# 15_-_PWR_3V3_1V375.net
KiCad netlist of a schematic drawn in Altium Designer
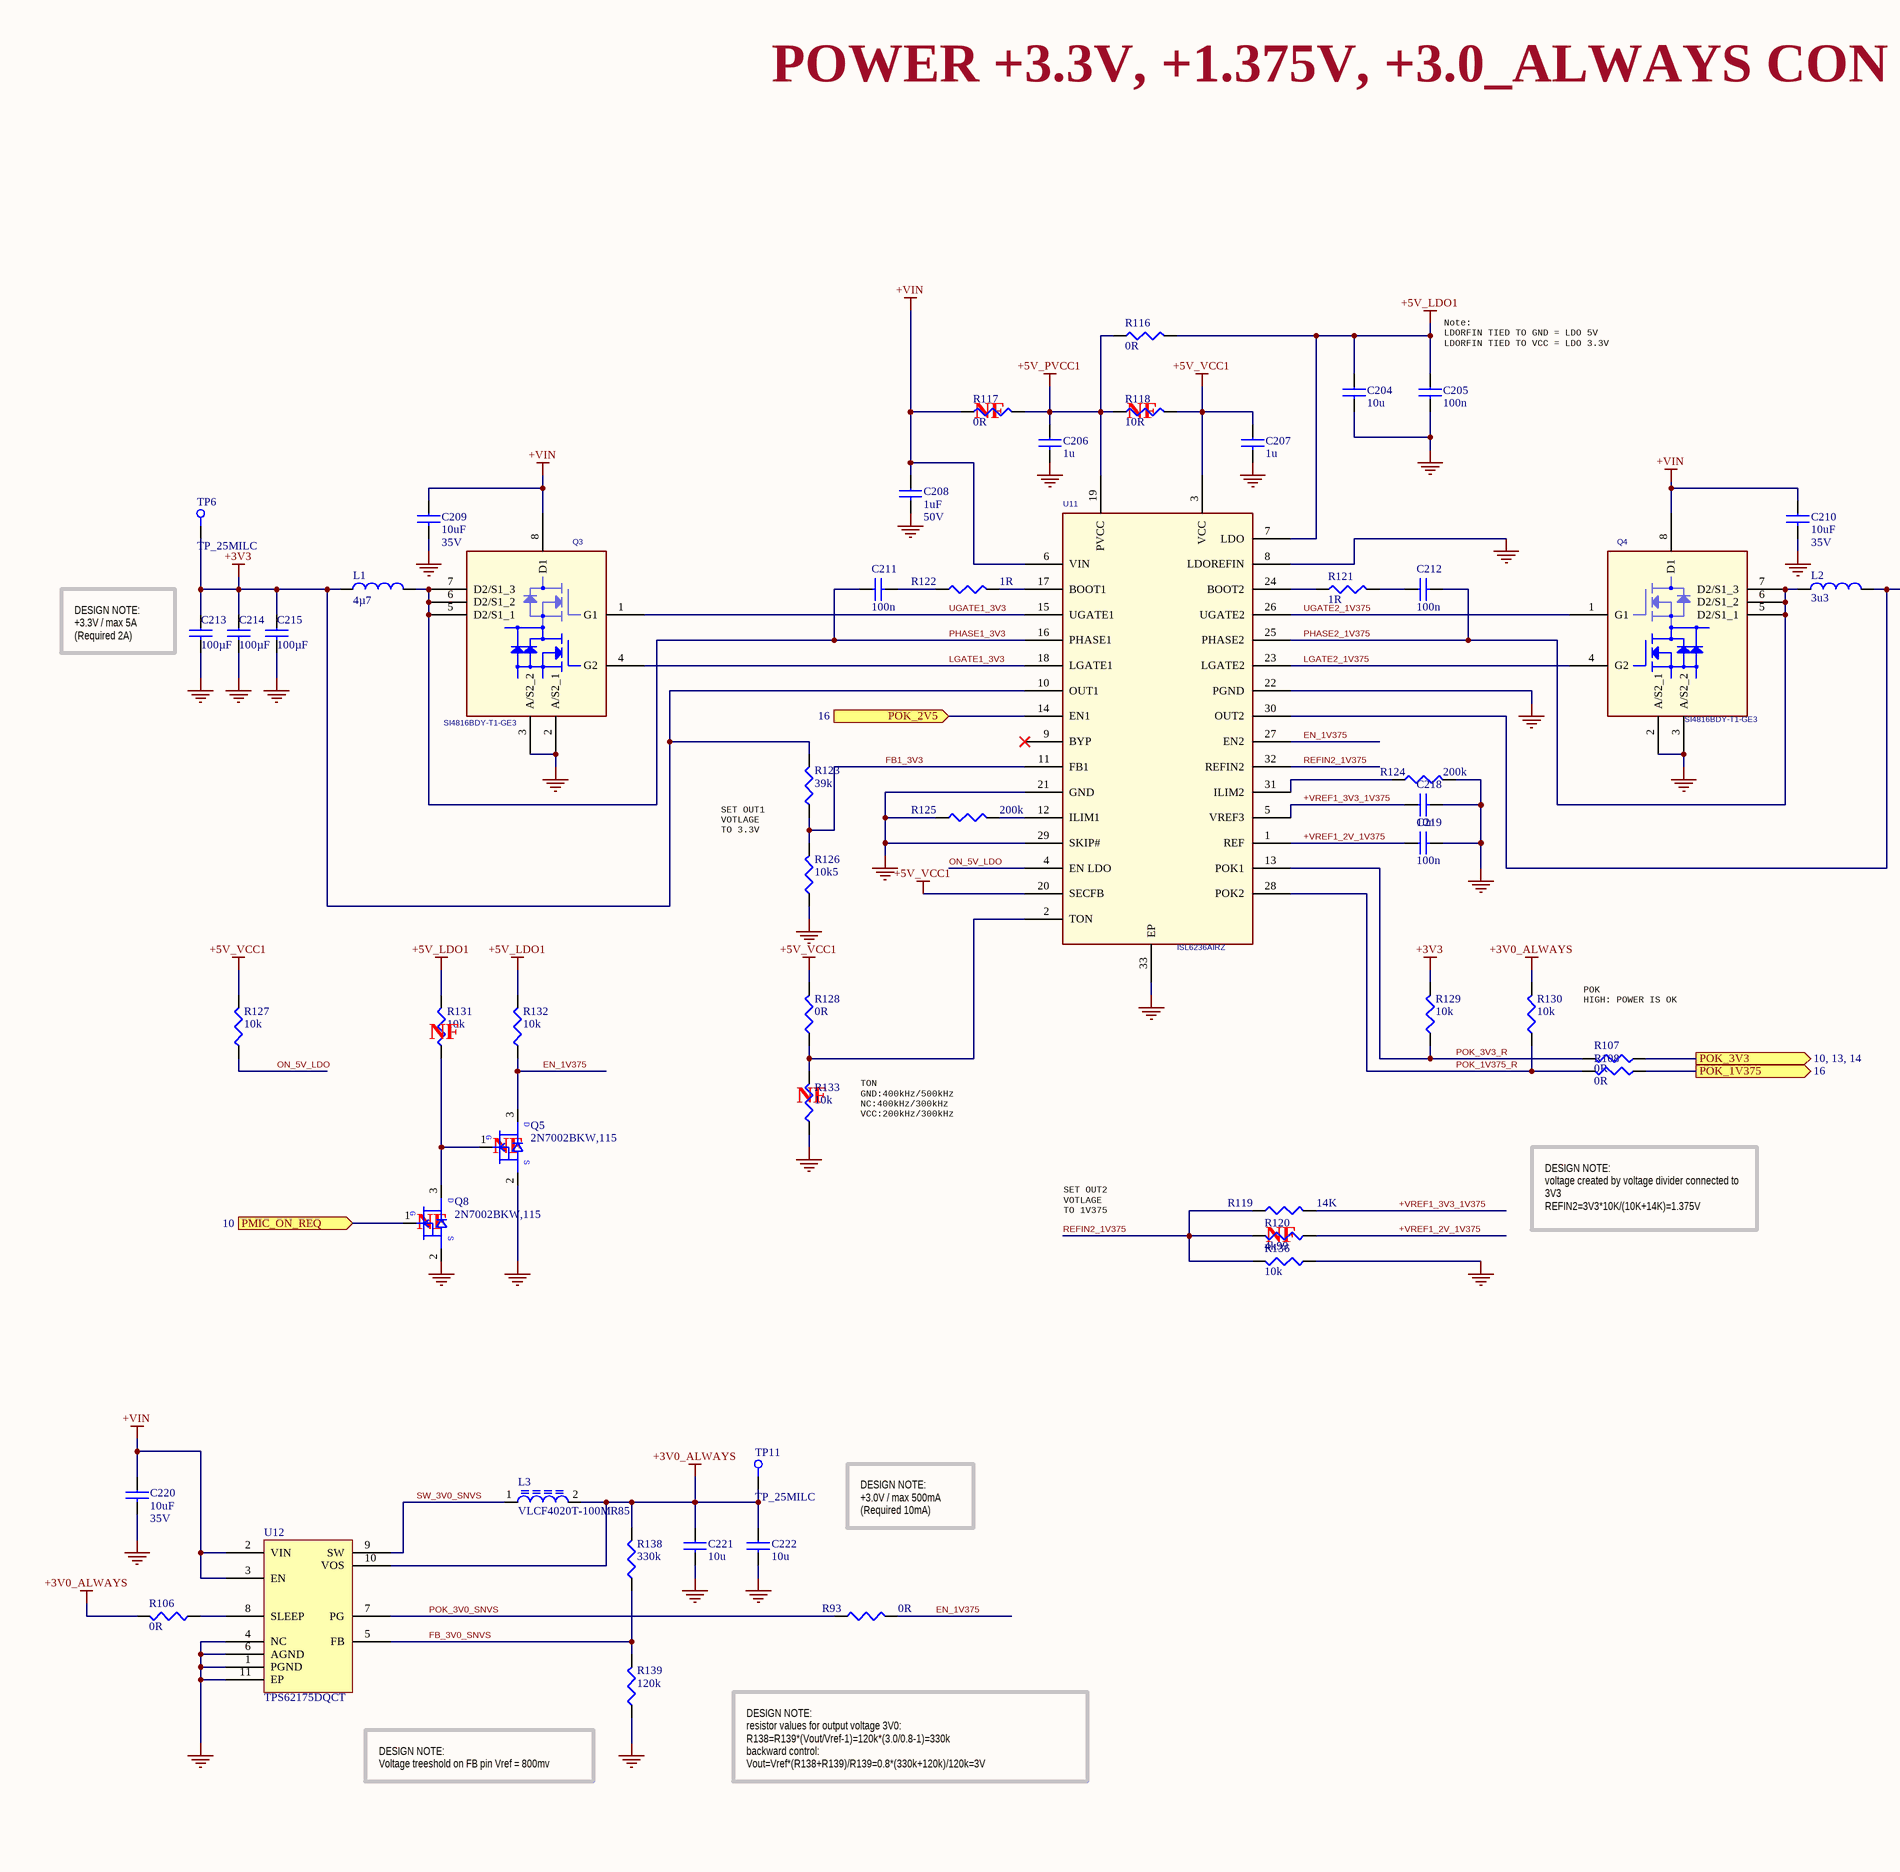
[diagram p0: [15] - PWR 3V3, 1V375.SchDoc, left]
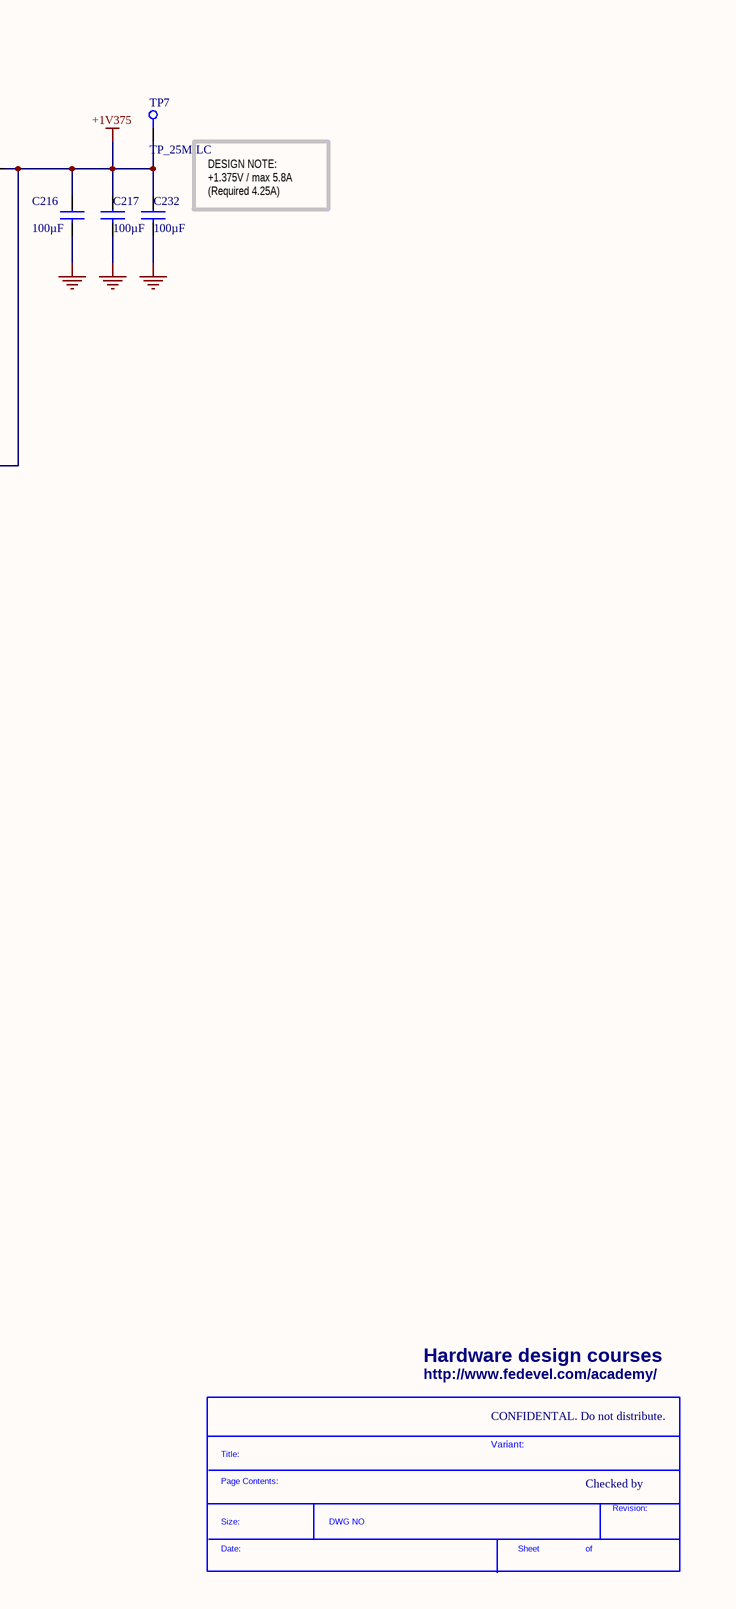
[diagram p1: [15] - PWR 3V3, 1V375.SchDoc, right]

(export (version "E")
  (design (tool "Eeschema 10.0.6"))
  (components
    (comp (ref "C204")
      (value "10u")
      (footprint "C0603")
      (description "CAP CER 10UF 6.3V X5R 20% 0603")
      (fields
        (field (name "MANUFACTURER") "TDK Corporation")
        (field (name "MANUFACTURER PART NUMBER") "C1608X5R0J106M")
      )
      (libsource (lib "iMX6 Rex_V1I1") (part "C1608X5R0J106M"))
    )
    (comp (ref "C205")
      (value "100n")
      (footprint "C0402")
      (description "CAP CER .10UF 50V X5R 10% 0402")
      (fields
        (field (name "MANUFACTURER") "TDK Corporation")
        (field (name "MANUFACTURER PART NUMBER") "C1005X5R1H104K")
      )
      (libsource (lib "iMX6 Rex_V1I1") (part "C1005X5R1H104K"))
    )
    (comp (ref "C206")
      (value "1u")
      (footprint "C0402")
      (description "CAP CER 1.0UF 16V X5R 0402")
      (fields
        (field (name "MANUFACTURER") "TDK Corporation")
        (field (name "MANUFACTURER PART NUMBER") "C1005X5R1C105K")
      )
      (libsource (lib "iMX6 Rex_V1I1") (part "C1005X5R1C105K"))
    )
    (comp (ref "C207")
      (value "1u")
      (footprint "C0402")
      (description "CAP CER 1.0UF 16V X5R 0402")
      (fields
        (field (name "MANUFACTURER") "TDK Corporation")
        (field (name "MANUFACTURER PART NUMBER") "C1005X5R1C105K")
      )
      (libsource (lib "iMX6 Rex_V1I1") (part "C1005X5R1C105K"))
    )
    (comp (ref "C208")
      (value "1uF")
      (footprint "C0805")
      (description "CAP CER 1UF 50V X7R 0805")
      (fields
        (field (name "MANUFACTURER") "Murata Electronics North America")
        (field (name "MANUFACTURER PART NUMBER") "GRM21BR71H105KA12L")
        (field (name "VOLTAGE - RATED") "50V")
      )
      (libsource (lib "iMX6 Rex_V1I1") (part "GRM21BR71H105KA12L"))
    )
    (comp (ref "C209")
      (value "10uF")
      (footprint "C1206")
      (description "CAP CER 10UF 35V X5R 1206")
      (fields
        (field (name "MANUFACTURER") "Murata Electronics North America")
        (field (name "MANUFACTURER PART NUMBER") "GRM31CR6YA106KA12L")
        (field (name "VOLTAGE - RATED") "35V")
      )
      (libsource (lib "iMX6 Rex_V1I1") (part "GRM31CR6YA106KA12L"))
    )
    (comp (ref "C210")
      (value "10uF")
      (footprint "C1206")
      (description "CAP CER 10UF 35V X5R 1206")
      (fields
        (field (name "MANUFACTURER") "Murata Electronics North America")
        (field (name "MANUFACTURER PART NUMBER") "GRM31CR6YA106KA12L")
        (field (name "VOLTAGE - RATED") "35V")
      )
      (libsource (lib "iMX6 Rex_V1I1") (part "GRM31CR6YA106KA12L"))
    )
    (comp (ref "C211")
      (value "100n")
      (footprint "C0402")
      (description "CAP CER .10UF 50V X5R 10% 0402")
      (fields
        (field (name "MANUFACTURER") "TDK Corporation")
        (field (name "MANUFACTURER PART NUMBER") "C1005X5R1H104K")
      )
      (libsource (lib "iMX6 Rex_V1I1") (part "C1005X5R1H104K"))
    )
    (comp (ref "C212")
      (value "100n")
      (footprint "C0402")
      (description "CAP CER .10UF 50V X5R 10% 0402")
      (fields
        (field (name "MANUFACTURER") "TDK Corporation")
        (field (name "MANUFACTURER PART NUMBER") "C1005X5R1H104K")
      )
      (libsource (lib "iMX6 Rex_V1I1") (part "C1005X5R1H104K"))
    )
    (comp (ref "C213")
      (value "100µF")
      (footprint "C1206")
      (description "CAP CER 100UF 10V X5R 20% 1206")
      (fields
        (field (name "MANUFACTURER") "TDK Corporation")
        (field (name "MANUFACTURER PART NUMBER") "C3216X5R1A107M")
      )
      (libsource (lib "iMX6 Rex_V1I1") (part "C3216X5R1A107M"))
    )
    (comp (ref "C214")
      (value "100µF")
      (footprint "C1206")
      (description "CAP CER 100UF 10V X5R 20% 1206")
      (fields
        (field (name "MANUFACTURER") "TDK Corporation")
        (field (name "MANUFACTURER PART NUMBER") "C3216X5R1A107M")
      )
      (libsource (lib "iMX6 Rex_V1I1") (part "C3216X5R1A107M"))
    )
    (comp (ref "C215")
      (value "100µF")
      (footprint "C1206")
      (description "CAP CER 100UF 10V X5R 20% 1206")
      (fields
        (field (name "MANUFACTURER") "TDK Corporation")
        (field (name "MANUFACTURER PART NUMBER") "C3216X5R1A107M")
      )
      (libsource (lib "iMX6 Rex_V1I1") (part "C3216X5R1A107M"))
    )
    (comp (ref "C216")
      (value "100µF")
      (footprint "C1206")
      (description "CAP CER 100UF 10V X5R 20% 1206")
      (fields
        (field (name "MANUFACTURER") "TDK Corporation")
        (field (name "MANUFACTURER PART NUMBER") "C3216X5R1A107M")
      )
      (libsource (lib "iMX6 Rex_V1I1") (part "C3216X5R1A107M"))
    )
    (comp (ref "C217")
      (value "100µF")
      (footprint "C1206")
      (description "CAP CER 100UF 10V X5R 20% 1206")
      (fields
        (field (name "MANUFACTURER") "TDK Corporation")
        (field (name "MANUFACTURER PART NUMBER") "C3216X5R1A107M")
      )
      (libsource (lib "iMX6 Rex_V1I1") (part "C3216X5R1A107M"))
    )
    (comp (ref "C218")
      (value "10n")
      (footprint "C0402")
      (description "CAP CER 10000PF 16V X7R 10% 0402")
      (fields
        (field (name "MANUFACTURER") "TDK Corporation")
        (field (name "MANUFACTURER PART NUMBER") "C1005X7R1C103K")
      )
      (libsource (lib "iMX6 Rex_V1I1") (part "C1005X7R1C103K"))
    )
    (comp (ref "C219")
      (value "100n")
      (footprint "C0402")
      (description "CAP CER .10UF 50V X5R 10% 0402")
      (fields
        (field (name "MANUFACTURER") "TDK Corporation")
        (field (name "MANUFACTURER PART NUMBER") "C1005X5R1H104K")
      )
      (libsource (lib "iMX6 Rex_V1I1") (part "C1005X5R1H104K"))
    )
    (comp (ref "C220")
      (value "10uF")
      (footprint "C1206")
      (description "CAP CER 10UF 35V X5R 1206")
      (fields
        (field (name "MANUFACTURER") "Murata Electronics North America")
        (field (name "MANUFACTURER PART NUMBER") "GRM31CR6YA106KA12L")
        (field (name "VOLTAGE - RATED") "35V")
      )
      (libsource (lib "iMX6 Rex_V1I1") (part "GRM31CR6YA106KA12L"))
    )
    (comp (ref "C221")
      (value "10u")
      (footprint "C0603")
      (description "CAP CER 10UF 6.3V X5R 20% 0603")
      (fields
        (field (name "MANUFACTURER") "TDK Corporation")
        (field (name "MANUFACTURER PART NUMBER") "C1608X5R0J106M")
      )
      (libsource (lib "iMX6 Rex_V1I1") (part "C1608X5R0J106M"))
    )
    (comp (ref "C222")
      (value "10u")
      (footprint "C0603")
      (description "CAP CER 10UF 6.3V X5R 20% 0603")
      (fields
        (field (name "MANUFACTURER") "TDK Corporation")
        (field (name "MANUFACTURER PART NUMBER") "C1608X5R0J106M")
      )
      (libsource (lib "iMX6 Rex_V1I1") (part "C1608X5R0J106M"))
    )
    (comp (ref "C232")
      (value "100µF")
      (footprint "C1206")
      (description "CAP CER 100UF 10V X5R 20% 1206")
      (fields
        (field (name "MANUFACTURER") "TDK Corporation")
        (field (name "MANUFACTURER PART NUMBER") "C3216X5R1A107M")
      )
      (libsource (lib "iMX6 Rex_V1I1") (part "C3216X5R1A107M"))
    )
    (comp (ref "L1")
      (value "4µ7")
      (footprint "IHLP_255MILx270MIL")
      (description "INDUCTOR POWER 4.7UH 5.5A SMD")
      (fields
        (field (name "MANUFACTURER") "Vishay/Dale")
        (field (name "MANUFACTURER PART NUMBER") "IHLP2525CZER4R7M01")
      )
      (libsource (lib "iMX6 Rex_V1I1") (part "IHLP2525CZER4R7M01"))
    )
    (comp (ref "L2")
      (value "3u3")
      (footprint "IHLP_255MILx270MIL")
      (description "INDUCTOR POWER 3.3UH 6A SMD")
      (fields
        (field (name "MANUFACTURER") "Vishay Dale")
        (field (name "MANUFACTURER PART NUMBER") "IHLP2525CZER3R3M01")
        (field (name ".CHECKED PCB") "RF")
        (field (name ".CHECKED SCH") "RF")
      )
      (libsource (lib "iMX6 Rex_V1I1") (part "IHLP2525CZER3R3M01"))
    )
    (comp (ref "L3")
      (value "VLCF4020T-100MR85")
      (footprint "VLCF4020")
      (description "INDUCTOR POWER 10UH .85A SMD")
      (fields
        (field (name "MANUFACTURER") "TDK Corporation")
        (field (name "TOLERANCE") "±20%")
        (field (name ".CREATOR") "MM")
        (field (name ".CHECKED PCB") "MM, checked by RF")
        (field (name ".CHECKED SCH") "MM, checked by RF")
      )
      (libsource (lib "iMX6 Rex_V1I1") (part "VLCF4020T-100MR85"))
    )
    (comp (ref "Q3")
      (value "SI4816BDY-T1-GE3")
      (footprint "8_SOIC_3.9MM")
      (description "MOSFET DL N-CH 30V 6.8A 8-SOIC")
      (fields (field (name "MANUFACTURER") "Vishay/Siliconix"))
      (libsource (lib "iMX6 Rex_V1I1") (part "SI4816BDY-T1-GE3"))
    )
    (comp (ref "Q4")
      (value "SI4816BDY-T1-GE3")
      (footprint "8_SOIC_3.9MM")
      (description "MOSFET DL N-CH 30V 6.8A 8-SOIC")
      (fields (field (name "MANUFACTURER") "Vishay/Siliconix"))
      (libsource (lib "iMX6 Rex_V1I1") (part "SI4816BDY-T1-GE3"))
    )
    (comp (ref "Q5")
      (value "2N7002BKW,115")
      (footprint "SC70_SOT323")
      (description "MOSFET N-CH 60V 310MA SOT323")
      (fields
        (field (name "MANUFACTURER") "NXP Semiconductors")
        (field (name ".CHECKED PCB") "RF")
        (field (name ".CHECKED SCH") "RF")
      )
      (libsource (lib "iMX6 Rex_V1I1") (part "2N7002BKW,115"))
    )
    (comp (ref "Q8")
      (value "2N7002BKW,115")
      (footprint "SC70_SOT323")
      (description "MOSFET N-CH 60V 310MA SOT323")
      (fields
        (field (name "MANUFACTURER") "NXP Semiconductors")
        (field (name ".CHECKED PCB") "RF")
        (field (name ".CHECKED SCH") "RF")
      )
      (libsource (lib "iMX6 Rex_V1I1") (part "2N7002BKW,115"))
    )
    (comp (ref "R93")
      (value "0R")
      (footprint "R0402")
      (description "RES 0.0 OHM 1/16W 0402 SMD")
      (fields
        (field (name "MANUFACTURER") "Yageo")
        (field (name "MANUFACTURER PART NUMBER") "RC0402JR-070RL")
      )
      (libsource (lib "iMX6 Rex_V1I1") (part "RC0402JR-070RL"))
    )
    (comp (ref "R106")
      (value "0R")
      (footprint "R0402")
      (description "RES 0.0 OHM 1/16W 0402 SMD")
      (fields
        (field (name "MANUFACTURER") "Yageo")
        (field (name "MANUFACTURER PART NUMBER") "RC0402JR-070RL")
      )
      (libsource (lib "iMX6 Rex_V1I1") (part "RC0402JR-070RL"))
    )
    (comp (ref "R107")
      (value "0R")
      (footprint "R0402")
      (description "RES 0.0 OHM 1/16W 0402 SMD")
      (fields
        (field (name "MANUFACTURER") "Yageo")
        (field (name "MANUFACTURER PART NUMBER") "RC0402JR-070RL")
      )
      (libsource (lib "iMX6 Rex_V1I1") (part "RC0402JR-070RL"))
    )
    (comp (ref "R108")
      (value "0R")
      (footprint "R0402")
      (description "RES 0.0 OHM 1/16W 0402 SMD")
      (fields
        (field (name "MANUFACTURER") "Yageo")
        (field (name "MANUFACTURER PART NUMBER") "RC0402JR-070RL")
      )
      (libsource (lib "iMX6 Rex_V1I1") (part "RC0402JR-070RL"))
    )
    (comp (ref "R116")
      (value "0R")
      (footprint "R0402")
      (description "RES 0.0 OHM 1/16W 0402 SMD")
      (fields
        (field (name "MANUFACTURER") "Yageo")
        (field (name "MANUFACTURER PART NUMBER") "RC0402JR-070RL")
      )
      (libsource (lib "iMX6 Rex_V1I1") (part "RC0402JR-070RL"))
    )
    (comp (ref "R117")
      (value "0R")
      (footprint "R0402")
      (description "RES 0.0 OHM 1/16W 0402 SMD")
      (fields
        (field (name "MANUFACTURER") "Yageo")
        (field (name "MANUFACTURER PART NUMBER") "RC0402JR-070RL")
      )
      (libsource (lib "iMX6 Rex_V1I1") (part "RC0402JR-070RL"))
    )
    (comp (ref "R118")
      (value "10R")
      (footprint "R0402")
      (description "RES 10.0 OHM 1/16W 1% 0402 SMD")
      (fields
        (field (name "MANUFACTURER") "Yageo")
        (field (name "MANUFACTURER PART NUMBER") "RC0402FR-0710RL")
      )
      (libsource (lib "iMX6 Rex_V1I1") (part "RC0402FR-0710RL"))
    )
    (comp (ref "R119")
      (value "14K")
      (footprint "R0402")
      (description "RES 14.0K OHM 1/16W 1% 0402 SMD")
      (fields
        (field (name "MANUFACTURER") "Yageo")
        (field (name "MANUFACTURER PART NUMBER") "RC0402FR-0714KL")
        (field (name "CREATOR") "MM")
        (field (name ".CHECKED PCB") "RF, used by MM")
        (field (name ".CHECKED SCH") "MM, checked by RF")
        (field (name ".CREATOR") "MM")
      )
      (libsource (lib "iMX6 Rex_V1I1") (part "RC0402FR-0714KL"))
    )
    (comp (ref "R120")
      (value "4k99")
      (footprint "R0402")
      (description "RES TF 4.99K OHM 1% 1/16W 0402")
      (fields
        (field (name "MANUFACTURER") "Stackpole Electronics Inc")
        (field (name "MANUFACTURER PART NUMBER") "RMCF0402FT4K99")
      )
      (libsource (lib "iMX6 Rex_V1I1") (part "RMCF0402FT4K99"))
    )
    (comp (ref "R121")
      (value "1R")
      (footprint "R0402")
      (description "RES 1.00 OHM 1/16W 1% 0402 SM")
      (fields
        (field (name "MANUFACTURER") "Yageo")
        (field (name "MANUFACTURER PART NUMBER") "RC0402FR-071RL")
      )
      (libsource (lib "iMX6 Rex_V1I1") (part "RC0402FR-071RL"))
    )
    (comp (ref "R122")
      (value "1R")
      (footprint "R0402")
      (description "RES 1.00 OHM 1/16W 1% 0402 SM")
      (fields
        (field (name "MANUFACTURER") "Yageo")
        (field (name "MANUFACTURER PART NUMBER") "RC0402FR-071RL")
      )
      (libsource (lib "iMX6 Rex_V1I1") (part "RC0402FR-071RL"))
    )
    (comp (ref "R123")
      (value "39k")
      (footprint "R0402")
      (description "RES 39.0K OHM 1/16W 1% 0402 SMD")
      (fields
        (field (name "MANUFACTURER") "Yageo")
        (field (name "MANUFACTURER PART NUMBER") "RC0402FR-0739KL")
      )
      (libsource (lib "iMX6 Rex_V1I1") (part "RC0402FR-0739KL"))
    )
    (comp (ref "R124")
      (value "200k")
      (footprint "R0402")
      (description "RES 200K OHM 1/16W 1% 0402 SMD")
      (fields
        (field (name "MANUFACTURER") "Yageo")
        (field (name "MANUFACTURER PART NUMBER") "RC0402FR-07200KL")
      )
      (libsource (lib "iMX6 Rex_V1I1") (part "RC0402FR-07200KL"))
    )
    (comp (ref "R125")
      (value "200k")
      (footprint "R0402")
      (description "RES 200K OHM 1/16W 1% 0402 SMD")
      (fields
        (field (name "MANUFACTURER") "Yageo")
        (field (name "MANUFACTURER PART NUMBER") "RC0402FR-07200KL")
      )
      (libsource (lib "iMX6 Rex_V1I1") (part "RC0402FR-07200KL"))
    )
    (comp (ref "R126")
      (value "10k5")
      (footprint "R0402")
      (description "RES 10.5K OHM 1/16W 1% 0402 SMD")
      (fields
        (field (name "MANUFACTURER") "Vishay/Dale")
        (field (name "MANUFACTURER PART NUMBER") "CRCW040210K5FKED")
      )
      (libsource (lib "iMX6 Rex_V1I1") (part "CRCW040210K5FKED"))
    )
    (comp (ref "R127")
      (value "10k")
      (footprint "R0402")
      (description "RES 10.0K OHM 1/16W 1% 0402 SMD")
      (fields
        (field (name "MANUFACTURER") "Yageo")
        (field (name "MANUFACTURER PART NUMBER") "RC0402FR-0710KL")
      )
      (libsource (lib "iMX6 Rex_V1I1") (part "RC0402FR-0710KL"))
    )
    (comp (ref "R128")
      (value "0R")
      (footprint "R0402")
      (description "RES 0.0 OHM 1/16W 0402 SMD")
      (fields
        (field (name "MANUFACTURER") "Yageo")
        (field (name "MANUFACTURER PART NUMBER") "RC0402JR-070RL")
      )
      (libsource (lib "iMX6 Rex_V1I1") (part "RC0402JR-070RL"))
    )
    (comp (ref "R129")
      (value "10k")
      (footprint "R0402")
      (description "RES 10.0K OHM 1/16W 1% 0402 SMD")
      (fields
        (field (name "MANUFACTURER") "Yageo")
        (field (name "MANUFACTURER PART NUMBER") "RC0402FR-0710KL")
      )
      (libsource (lib "iMX6 Rex_V1I1") (part "RC0402FR-0710KL"))
    )
    (comp (ref "R130")
      (value "10k")
      (footprint "R0402")
      (description "RES 10.0K OHM 1/16W 1% 0402 SMD")
      (fields
        (field (name "MANUFACTURER") "Yageo")
        (field (name "MANUFACTURER PART NUMBER") "RC0402FR-0710KL")
      )
      (libsource (lib "iMX6 Rex_V1I1") (part "RC0402FR-0710KL"))
    )
    (comp (ref "R131")
      (value "10k")
      (footprint "R0402")
      (description "RES 10.0K OHM 1/16W 1% 0402 SMD")
      (fields
        (field (name "MANUFACTURER") "Yageo")
        (field (name "MANUFACTURER PART NUMBER") "RC0402FR-0710KL")
      )
      (libsource (lib "iMX6 Rex_V1I1") (part "RC0402FR-0710KL"))
    )
    (comp (ref "R132")
      (value "10k")
      (footprint "R0402")
      (description "RES 10.0K OHM 1/16W 1% 0402 SMD")
      (fields
        (field (name "MANUFACTURER") "Yageo")
        (field (name "MANUFACTURER PART NUMBER") "RC0402FR-0710KL")
      )
      (libsource (lib "iMX6 Rex_V1I1") (part "RC0402FR-0710KL"))
    )
    (comp (ref "R133")
      (value "10k")
      (footprint "R0402")
      (description "RES 10.0K OHM 1/16W 1% 0402 SMD")
      (fields
        (field (name "MANUFACTURER") "Yageo")
        (field (name "MANUFACTURER PART NUMBER") "RC0402FR-0710KL")
      )
      (libsource (lib "iMX6 Rex_V1I1") (part "RC0402FR-0710KL"))
    )
    (comp (ref "R136")
      (value "10k")
      (footprint "R0402")
      (description "RES 10.0K OHM 1/16W 1% 0402 SMD")
      (fields
        (field (name "MANUFACTURER") "Yageo")
        (field (name "MANUFACTURER PART NUMBER") "RC0402FR-0710KL")
      )
      (libsource (lib "iMX6 Rex_V1I1") (part "RC0402FR-0710KL"))
    )
    (comp (ref "R138")
      (value "330k")
      (footprint "R0402")
      (description "RES 330K OHM 1/16W 1% 0402 SMD")
      (fields
        (field (name "MANUFACTURER") "Vishay Dale")
        (field (name "MANUFACTURER PART NUMBER") "CRCW0402330KFKED")
        (field (name ".CHECKED PCB") "RF")
        (field (name ".CHECKED SCH") "RF")
      )
      (libsource (lib "iMX6 Rex_V1I1") (part "CRCW0402330KFKED"))
    )
    (comp (ref "R139")
      (value "120k")
      (footprint "R0402")
      (description "RES 120K OHM 1/16W 1% 0402 SMD")
      (fields
        (field (name "MANUFACTURER") "Yageo")
        (field (name "MANUFACTURER PART NUMBER") "RC0402FR-07120KL")
        (field (name ".CHECKED PCB") "OK RF")
        (field (name ".CHECKED SCH") "RF")
      )
      (libsource (lib "iMX6 Rex_V1I1") (part "RC0402FR-07120KL"))
    )
    (comp (ref "TP6")
      (value "TP_25MILC")
      (footprint "TP_25C")
      (description "Test Point 25mil")
      (libsource (lib "iMX6 Rex_V1I1") (part "TP_25MILC"))
    )
    (comp (ref "TP7")
      (value "TP_25MILC")
      (footprint "TP_25C")
      (description "Test Point 25mil")
      (libsource (lib "iMX6 Rex_V1I1") (part "TP_25MILC"))
    )
    (comp (ref "TP11")
      (value "TP_25MILC")
      (footprint "TP_25C")
      (description "Test Point 25mil")
      (libsource (lib "iMX6 Rex_V1I1") (part "TP_25MILC"))
    )
    (comp (ref "U11")
      (value "ISL6236AIRZ")
      (footprint "32_VFQFN_EXPOSED_PAD")
      (description "IC MAIN PWR CTRLR QUAD 32-QFN")
      (fields (field (name "MANUFACTURER") "Intersil"))
      (libsource (lib "iMX6 Rex_V1I1") (part "ISL6236AIRZ"))
    )
    (comp (ref "U12")
      (value "TPS62175DQCT")
      (footprint "DQC_PWSON-N10")
      (description "IC REG BUCK SYNC ADJ 0.5A 10WSON")
      (fields
        (field (name "MANUFACTURER") "Texas Instruments")
        (field (name ".CREATOR") "MM")
        (field (name ".CHECKED PCB") "MM, checked by RF")
        (field (name ".CHECKED SCH") "MM, checked by RF")
      )
      (libsource (lib "iMX6 Rex_V1I1") (part "TPS62175DQCT"))
    )
  )
  (nets
    (net (code "1") (name "+1V375") (class "Default")
      (node (ref "C216") (pin "1") (pinfunction "1_1") (pintype "passive"))
      (node (ref "C217") (pin "1") (pinfunction "1_1") (pintype "passive"))
      (node (ref "C232") (pin "1") (pinfunction "1_1") (pintype "passive"))
      (node (ref "L2") (pin "2") (pinfunction "2_2") (pintype "passive"))
      (node (ref "TP7") (pin "1") (pinfunction "1_1") (pintype "passive"))
      (node (ref "U11") (pin "30") (pinfunction "OUT2_30") (pintype "passive"))
    )
    (net (code "2") (name "+3V0_ALWAYS") (class "Default")
      (node (ref "C221") (pin "1") (pinfunction "1_1") (pintype "passive"))
      (node (ref "C222") (pin "1") (pinfunction "1_1") (pintype "passive"))
      (node (ref "L3") (pin "2") (pinfunction "2_2") (pintype "passive"))
      (node (ref "R106") (pin "2") (pinfunction "2_2") (pintype "passive"))
      (node (ref "R130") (pin "2") (pinfunction "2_2") (pintype "passive"))
      (node (ref "R138") (pin "2") (pinfunction "2_2") (pintype "passive"))
      (node (ref "TP11") (pin "1") (pinfunction "1_1") (pintype "passive"))
      (node (ref "U12") (pin "10") (pinfunction "VOS_10") (pintype "passive"))
    )
    (net (code "3") (name "+3V3") (class "Default")
      (node (ref "C213") (pin "1") (pinfunction "1_1") (pintype "passive"))
      (node (ref "C214") (pin "1") (pinfunction "1_1") (pintype "passive"))
      (node (ref "C215") (pin "1") (pinfunction "1_1") (pintype "passive"))
      (node (ref "L1") (pin "1") (pinfunction "1_1") (pintype "passive"))
      (node (ref "R123") (pin "2") (pinfunction "2_2") (pintype "passive"))
      (node (ref "R129") (pin "2") (pinfunction "2_2") (pintype "passive"))
      (node (ref "TP6") (pin "1") (pinfunction "1_1") (pintype "passive"))
      (node (ref "U11") (pin "10") (pinfunction "OUT1_10") (pintype "passive"))
    )
    (net (code "4") (name "+5V_LDO1") (class "Default")
      (node (ref "C204") (pin "1") (pinfunction "1_1") (pintype "passive"))
      (node (ref "C205") (pin "1") (pinfunction "1_1") (pintype "passive"))
      (node (ref "R116") (pin "2") (pinfunction "2_2") (pintype "passive"))
      (node (ref "R131") (pin "2") (pinfunction "2_2") (pintype "passive"))
      (node (ref "R132") (pin "2") (pinfunction "2_2") (pintype "passive"))
      (node (ref "U11") (pin "7") (pinfunction "LDO_7") (pintype "passive"))
    )
    (net (code "5") (name "+5V_PVCC1") (class "Default")
      (node (ref "C206") (pin "1") (pinfunction "1_1") (pintype "passive"))
      (node (ref "R116") (pin "1") (pinfunction "1_1") (pintype "passive"))
      (node (ref "R117") (pin "2") (pinfunction "2_2") (pintype "passive"))
      (node (ref "R118") (pin "1") (pinfunction "1_1") (pintype "passive"))
      (node (ref "U11") (pin "19") (pinfunction "PVCC_19") (pintype "passive"))
    )
    (net (code "6") (name "+5V_VCC1") (class "Default")
      (node (ref "C207") (pin "1") (pinfunction "1_1") (pintype "passive"))
      (node (ref "R118") (pin "2") (pinfunction "2_2") (pintype "passive"))
      (node (ref "R127") (pin "2") (pinfunction "2_2") (pintype "passive"))
      (node (ref "R128") (pin "2") (pinfunction "2_2") (pintype "passive"))
      (node (ref "U11") (pin "20") (pinfunction "SECFB_20") (pintype "passive"))
      (node (ref "U11") (pin "3") (pinfunction "VCC_3") (pintype "passive"))
    )
    (net (code "7") (name "+VIN") (class "Default")
      (node (ref "C208") (pin "1") (pinfunction "1_1") (pintype "passive"))
      (node (ref "C209") (pin "1") (pinfunction "1_1") (pintype "passive"))
      (node (ref "C210") (pin "1") (pinfunction "1_1") (pintype "passive"))
      (node (ref "C220") (pin "1") (pinfunction "1_1") (pintype "passive"))
      (node (ref "Q3") (pin "8") (pinfunction "D1_8") (pintype "passive"))
      (node (ref "Q4") (pin "8") (pinfunction "D1_8") (pintype "passive"))
      (node (ref "R117") (pin "1") (pinfunction "1_1") (pintype "passive"))
      (node (ref "U11") (pin "6") (pinfunction "VIN_6") (pintype "passive"))
      (node (ref "U12") (pin "2") (pinfunction "VIN_2") (pintype "passive"))
      (node (ref "U12") (pin "3") (pinfunction "EN_3") (pintype "passive"))
    )
    (net (code "8") (name "/+VREF1_2V_1V375") (class "Default")
      (node (ref "C219") (pin "1") (pinfunction "1_1") (pintype "passive"))
      (node (ref "R120") (pin "1") (pinfunction "1_1") (pintype "passive"))
      (node (ref "U11") (pin "1") (pinfunction "REF_1") (pintype "passive"))
    )
    (net (code "9") (name "/+VREF1_3V3_1V375") (class "Default")
      (node (ref "C218") (pin "1") (pinfunction "1_1") (pintype "passive"))
      (node (ref "R119") (pin "2") (pinfunction "2_2") (pintype "passive"))
      (node (ref "U11") (pin "5") (pinfunction "VREF3_5") (pintype "passive"))
    )
    (net (code "10") (name "/EN_1V375") (class "Default")
      (node (ref "Q5") (pin "3") (pinfunction "DRAIN_3") (pintype "passive"))
      (node (ref "R132") (pin "1") (pinfunction "1_1") (pintype "passive"))
      (node (ref "R93") (pin "2") (pinfunction "2_2") (pintype "passive"))
      (node (ref "U11") (pin "27") (pinfunction "EN2_27") (pintype "passive"))
    )
    (net (code "11") (name "/FB1_3V3") (class "Default")
      (node (ref "R123") (pin "1") (pinfunction "1_1") (pintype "passive"))
      (node (ref "R126") (pin "2") (pinfunction "2_2") (pintype "passive"))
      (node (ref "U11") (pin "11") (pinfunction "FB1_11") (pintype "passive"))
    )
    (net (code "12") (name "/FB_3V0_SNVS") (class "Default")
      (node (ref "R138") (pin "1") (pinfunction "1_1") (pintype "passive"))
      (node (ref "R139") (pin "2") (pinfunction "2_2") (pintype "passive"))
      (node (ref "U12") (pin "5") (pinfunction "FB_5") (pintype "passive"))
    )
    (net (code "13") (name "/LGATE1_3V3") (class "Default")
      (node (ref "Q3") (pin "4") (pinfunction "G2_4") (pintype "passive"))
      (node (ref "U11") (pin "18") (pinfunction "LGATE1_18") (pintype "passive"))
    )
    (net (code "14") (name "/LGATE2_1V375") (class "Default")
      (node (ref "Q4") (pin "4") (pinfunction "G2_4") (pintype "passive"))
      (node (ref "U11") (pin "23") (pinfunction "LGATE2_23") (pintype "passive"))
    )
    (net (code "15") (name "/ON_5V_LDO") (class "Default")
      (node (ref "R127") (pin "1") (pinfunction "1_1") (pintype "passive"))
      (node (ref "U11") (pin "4") (pinfunction "EN_LDO_4") (pintype "passive"))
    )
    (net (code "16") (name "/PHASE1_3V3") (class "Default")
      (node (ref "C211") (pin "1") (pinfunction "1_1") (pintype "passive"))
      (node (ref "L1") (pin "2") (pinfunction "2_2") (pintype "passive"))
      (node (ref "Q3") (pin "5") (pinfunction "D2/S1_1_5") (pintype "passive"))
      (node (ref "Q3") (pin "6") (pinfunction "D2/S1_2_6") (pintype "passive"))
      (node (ref "Q3") (pin "7") (pinfunction "D2/S1_3_7") (pintype "passive"))
      (node (ref "U11") (pin "16") (pinfunction "PHASE1_16") (pintype "passive"))
    )
    (net (code "17") (name "/PHASE2_1V375") (class "Default")
      (node (ref "C212") (pin "2") (pinfunction "2_2") (pintype "passive"))
      (node (ref "L2") (pin "1") (pinfunction "1_1") (pintype "passive"))
      (node (ref "Q4") (pin "5") (pinfunction "D2/S1_1_5") (pintype "passive"))
      (node (ref "Q4") (pin "6") (pinfunction "D2/S1_2_6") (pintype "passive"))
      (node (ref "Q4") (pin "7") (pinfunction "D2/S1_3_7") (pintype "passive"))
      (node (ref "U11") (pin "25") (pinfunction "PHASE2_25") (pintype "passive"))
    )
    (net (code "18") (name "/PMIC_ON_REQ") (class "Default")
      (node (ref "Q8") (pin "1") (pinfunction "GATE_1") (pintype "passive"))
    )
    (net (code "19") (name "/POK_1V375") (class "Default")
      (node (ref "R108") (pin "1") (pinfunction "1_1") (pintype "passive"))
    )
    (net (code "20") (name "/POK_1V375_R") (class "Default")
      (node (ref "R108") (pin "2") (pinfunction "2_2") (pintype "passive"))
      (node (ref "R130") (pin "1") (pinfunction "1_1") (pintype "passive"))
      (node (ref "U11") (pin "28") (pinfunction "POK2_28") (pintype "passive"))
    )
    (net (code "21") (name "/POK_2V5") (class "Default")
      (node (ref "U11") (pin "14") (pinfunction "EN1_14") (pintype "passive"))
    )
    (net (code "22") (name "/POK_3V0_SNVS") (class "Default")
      (node (ref "R93") (pin "1") (pinfunction "1_1") (pintype "passive"))
      (node (ref "U12") (pin "7") (pinfunction "PG_7") (pintype "passive"))
    )
    (net (code "23") (name "/POK_3V3") (class "Default")
      (node (ref "R107") (pin "1") (pinfunction "1_1") (pintype "passive"))
    )
    (net (code "24") (name "/POK_3V3_R") (class "Default")
      (node (ref "R107") (pin "2") (pinfunction "2_2") (pintype "passive"))
      (node (ref "R129") (pin "1") (pinfunction "1_1") (pintype "passive"))
      (node (ref "U11") (pin "13") (pinfunction "POK1_13") (pintype "passive"))
    )
    (net (code "25") (name "/REFIN2_1V375") (class "Default")
      (node (ref "R119") (pin "1") (pinfunction "1_1") (pintype "passive"))
      (node (ref "R120") (pin "2") (pinfunction "2_2") (pintype "passive"))
      (node (ref "R136") (pin "2") (pinfunction "2_2") (pintype "passive"))
      (node (ref "U11") (pin "32") (pinfunction "REFIN2_32") (pintype "passive"))
    )
    (net (code "26") (name "/SW_3V0_SNVS") (class "Default")
      (node (ref "L3") (pin "1") (pinfunction "1_1") (pintype "passive"))
      (node (ref "U12") (pin "9") (pinfunction "SW_9") (pintype "passive"))
    )
    (net (code "27") (name "/UGATE1_3V3") (class "Default")
      (node (ref "Q3") (pin "1") (pinfunction "G1_1") (pintype "passive"))
      (node (ref "U11") (pin "15") (pinfunction "UGATE1_15") (pintype "passive"))
    )
    (net (code "28") (name "/UGATE2_1V375") (class "Default")
      (node (ref "Q4") (pin "1") (pinfunction "G1_1") (pintype "passive"))
      (node (ref "U11") (pin "26") (pinfunction "UGATE2_26") (pintype "passive"))
    )
    (net (code "29") (name "GND") (class "Default")
      (node (ref "C204") (pin "2") (pinfunction "2_2") (pintype "passive"))
      (node (ref "C205") (pin "2") (pinfunction "2_2") (pintype "passive"))
      (node (ref "C206") (pin "2") (pinfunction "2_2") (pintype "passive"))
      (node (ref "C207") (pin "2") (pinfunction "2_2") (pintype "passive"))
      (node (ref "C208") (pin "2") (pinfunction "2_2") (pintype "passive"))
      (node (ref "C209") (pin "2") (pinfunction "2_2") (pintype "passive"))
      (node (ref "C210") (pin "2") (pinfunction "2_2") (pintype "passive"))
      (node (ref "C213") (pin "2") (pinfunction "2_2") (pintype "passive"))
      (node (ref "C214") (pin "2") (pinfunction "2_2") (pintype "passive"))
      (node (ref "C215") (pin "2") (pinfunction "2_2") (pintype "passive"))
      (node (ref "C216") (pin "2") (pinfunction "2_2") (pintype "passive"))
      (node (ref "C217") (pin "2") (pinfunction "2_2") (pintype "passive"))
      (node (ref "C218") (pin "2") (pinfunction "2_2") (pintype "passive"))
      (node (ref "C219") (pin "2") (pinfunction "2_2") (pintype "passive"))
      (node (ref "C220") (pin "2") (pinfunction "2_2") (pintype "passive"))
      (node (ref "C221") (pin "2") (pinfunction "2_2") (pintype "passive"))
      (node (ref "C222") (pin "2") (pinfunction "2_2") (pintype "passive"))
      (node (ref "C232") (pin "2") (pinfunction "2_2") (pintype "passive"))
      (node (ref "Q3") (pin "2") (pinfunction "A/S2_1_2") (pintype "passive"))
      (node (ref "Q3") (pin "3") (pinfunction "A/S2_2_3") (pintype "passive"))
      (node (ref "Q4") (pin "2") (pinfunction "A/S2_1_2") (pintype "passive"))
      (node (ref "Q4") (pin "3") (pinfunction "A/S2_2_3") (pintype "passive"))
      (node (ref "Q5") (pin "2") (pinfunction "SOURCE_2") (pintype "passive"))
      (node (ref "Q8") (pin "2") (pinfunction "SOURCE_2") (pintype "passive"))
      (node (ref "R124") (pin "2") (pinfunction "2_2") (pintype "passive"))
      (node (ref "R125") (pin "1") (pinfunction "1_1") (pintype "passive"))
      (node (ref "R126") (pin "1") (pinfunction "1_1") (pintype "passive"))
      (node (ref "R133") (pin "1") (pinfunction "1_1") (pintype "passive"))
      (node (ref "R136") (pin "1") (pinfunction "1_1") (pintype "passive"))
      (node (ref "R139") (pin "1") (pinfunction "1_1") (pintype "passive"))
      (node (ref "U11") (pin "21") (pinfunction "GND_21") (pintype "passive"))
      (node (ref "U11") (pin "22") (pinfunction "PGND_22") (pintype "passive"))
      (node (ref "U11") (pin "29") (pinfunction "SKIP#_29") (pintype "passive"))
      (node (ref "U11") (pin "33") (pinfunction "EP_33") (pintype "passive"))
      (node (ref "U11") (pin "8") (pinfunction "LDOREFIN_8") (pintype "passive"))
      (node (ref "U12") (pin "1") (pinfunction "PGND_1") (pintype "passive"))
      (node (ref "U12") (pin "11") (pinfunction "EP_11") (pintype "passive"))
      (node (ref "U12") (pin "4") (pinfunction "NC_4") (pintype "passive"))
      (node (ref "U12") (pin "6") (pinfunction "AGND_6") (pintype "passive"))
    )
    (net (code "30") (name "Net-(C211-Pad2)") (class "Default")
      (node (ref "C211") (pin "2") (pinfunction "2_2") (pintype "passive"))
      (node (ref "R122") (pin "1") (pinfunction "1_1") (pintype "passive"))
    )
    (net (code "31") (name "Net-(C212-Pad1)") (class "Default")
      (node (ref "C212") (pin "1") (pinfunction "1_1") (pintype "passive"))
      (node (ref "R121") (pin "2") (pinfunction "2_2") (pintype "passive"))
    )
    (net (code "32") (name "Net-(Q5-GATE)") (class "Default")
      (node (ref "Q5") (pin "1") (pinfunction "GATE_1") (pintype "passive"))
      (node (ref "Q8") (pin "3") (pinfunction "DRAIN_3") (pintype "passive"))
      (node (ref "R131") (pin "1") (pinfunction "1_1") (pintype "passive"))
    )
    (net (code "33") (name "Net-(U11-BOOT1)") (class "Default")
      (node (ref "R122") (pin "2") (pinfunction "2_2") (pintype "passive"))
      (node (ref "U11") (pin "17") (pinfunction "BOOT1_17") (pintype "passive"))
    )
    (net (code "34") (name "Net-(U11-BOOT2)") (class "Default")
      (node (ref "R121") (pin "1") (pinfunction "1_1") (pintype "passive"))
      (node (ref "U11") (pin "24") (pinfunction "BOOT2_24") (pintype "passive"))
    )
    (net (code "35") (name "Net-(U11-ILIM1)") (class "Default")
      (node (ref "R125") (pin "2") (pinfunction "2_2") (pintype "passive"))
      (node (ref "U11") (pin "12") (pinfunction "ILIM1_12") (pintype "passive"))
    )
    (net (code "36") (name "Net-(U11-ILIM2)") (class "Default")
      (node (ref "R124") (pin "1") (pinfunction "1_1") (pintype "passive"))
      (node (ref "U11") (pin "31") (pinfunction "ILIM2_31") (pintype "passive"))
    )
    (net (code "37") (name "Net-(U11-TON)") (class "Default")
      (node (ref "R128") (pin "1") (pinfunction "1_1") (pintype "passive"))
      (node (ref "R133") (pin "2") (pinfunction "2_2") (pintype "passive"))
      (node (ref "U11") (pin "2") (pinfunction "TON_2") (pintype "passive"))
    )
    (net (code "38") (name "Net-(U12-SLEEP)") (class "Default")
      (node (ref "R106") (pin "1") (pinfunction "1_1") (pintype "passive"))
      (node (ref "U12") (pin "8") (pinfunction "SLEEP_8") (pintype "passive"))
    )
    (net (code "39") (name "unconnected-(U11-BYP-Pad9)") (class "Default")
      (node (ref "U11") (pin "9") (pinfunction "BYP_9") (pintype "passive+no_connect"))
    )
  )
)
